# RTCC.net
KiCad netlist of a schematic drawn in Altium Designer
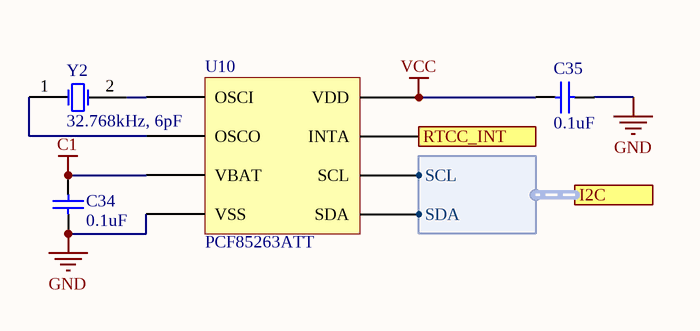
[diagram p0: RTCC.SchDoc]

(export (version "E")
  (design (tool "Eeschema 10.0.6"))
  (components
    (comp (ref "C34")
      (value "0.1uF")
      (footprint "C0603[1608X92]")
      (description "0.1uF 6.3V 10% 0603 (1608 Metric)")
      (fields (field (name "PARTNUMBER") "GRM188R70J104KA01D") (field (name "MANUFACTURER") "Murata"))
      (libsource (lib "Capacitors") (part "CAP_0.1uF_6.3V_0603_10%"))
    )
    (comp (ref "C35")
      (value "0.1uF")
      (footprint "C0603[1608X92]")
      (description "0.1uF 6.3V 10% 0603 (1608 Metric)")
      (fields (field (name "PARTNUMBER") "GRM188R70J104KA01D") (field (name "MANUFACTURER") "Murata"))
      (libsource (lib "Capacitors") (part "CAP_0.1uF_6.3V_0603_10%"))
    )
    (comp (ref "U10")
      (value "PCF85263ATT")
      (footprint "TSSOP-8")
      (description "Real Time Clock Real-Time Clock calendar")
      (fields (field (name "PARTNUMBER") "PCF85263ATT/AJ") (field (name "MANUFACTURER") "Texas Instruments"))
      (libsource (lib "ICs") (part "PCF85263ATT"))
    )
    (comp (ref "Y2")
      (value "32.768kHz, 6pF")
      (footprint "ST3215SB")
      (description "32.768kHz ±20ppm Crystal 6pF 60 kOhm -40°C ~ 85°C Surface Mount 2-SMD, No Lead (DFN, LCC)")
      (fields (field (name "MANUFACTURER") "AVX/Kyocera") (field (name "PARTNUMBER") "ST3215SB32768B0HPWB3"))
      (libsource (lib "Components") (part "ST3215SB32768B0HPWB3"))
    )
  )
  (nets
    (net (code "2") (name "/RTCC_INT") (class "Default")
      (node (ref "U10") (pin "7") (pinfunction "INTA_7") (pintype "passive"))
    )
    (net (code "3") (name "/SCL") (class "Default")
      (node (ref "U10") (pin "6") (pinfunction "SCL_6") (pintype "passive"))
    )
    (net (code "4") (name "/SDA") (class "Default")
      (node (ref "U10") (pin "5") (pinfunction "SDA_5") (pintype "passive"))
    )
    (net (code "6") (name "C1") (class "Default")
      (node (ref "C34") (pin "2") (pinfunction "2_2") (pintype "passive"))
      (node (ref "U10") (pin "3") (pinfunction "VBAT_3") (pintype "power_in"))
    )
    (net (code "7") (name "GND") (class "Default")
      (node (ref "C34") (pin "1") (pinfunction "1_1") (pintype "passive"))
      (node (ref "C35") (pin "2") (pinfunction "2_2") (pintype "passive"))
      (node (ref "U10") (pin "4") (pinfunction "VSS_4") (pintype "power_in"))
    )
    (net (code "8") (name "Net-(U10-OSCI)") (class "Default")
      (node (ref "U10") (pin "1") (pinfunction "OSCI_1") (pintype "passive"))
      (node (ref "Y2") (pin "2") (pinfunction "X2_2") (pintype "passive"))
    )
    (net (code "9") (name "Net-(U10-OSCO)") (class "Default")
      (node (ref "U10") (pin "2") (pinfunction "OSCO_2") (pintype "passive"))
      (node (ref "Y2") (pin "1") (pinfunction "X1_1") (pintype "passive"))
    )
    (net (code "10") (name "VCC") (class "Default")
      (node (ref "C35") (pin "1") (pinfunction "1_1") (pintype "passive"))
      (node (ref "U10") (pin "8") (pinfunction "VDD_8") (pintype "power_in"))
    )
  )
)
